# AirSystem8266PCB.net
KiCad netlist of a schematic drawn in Altium Designer
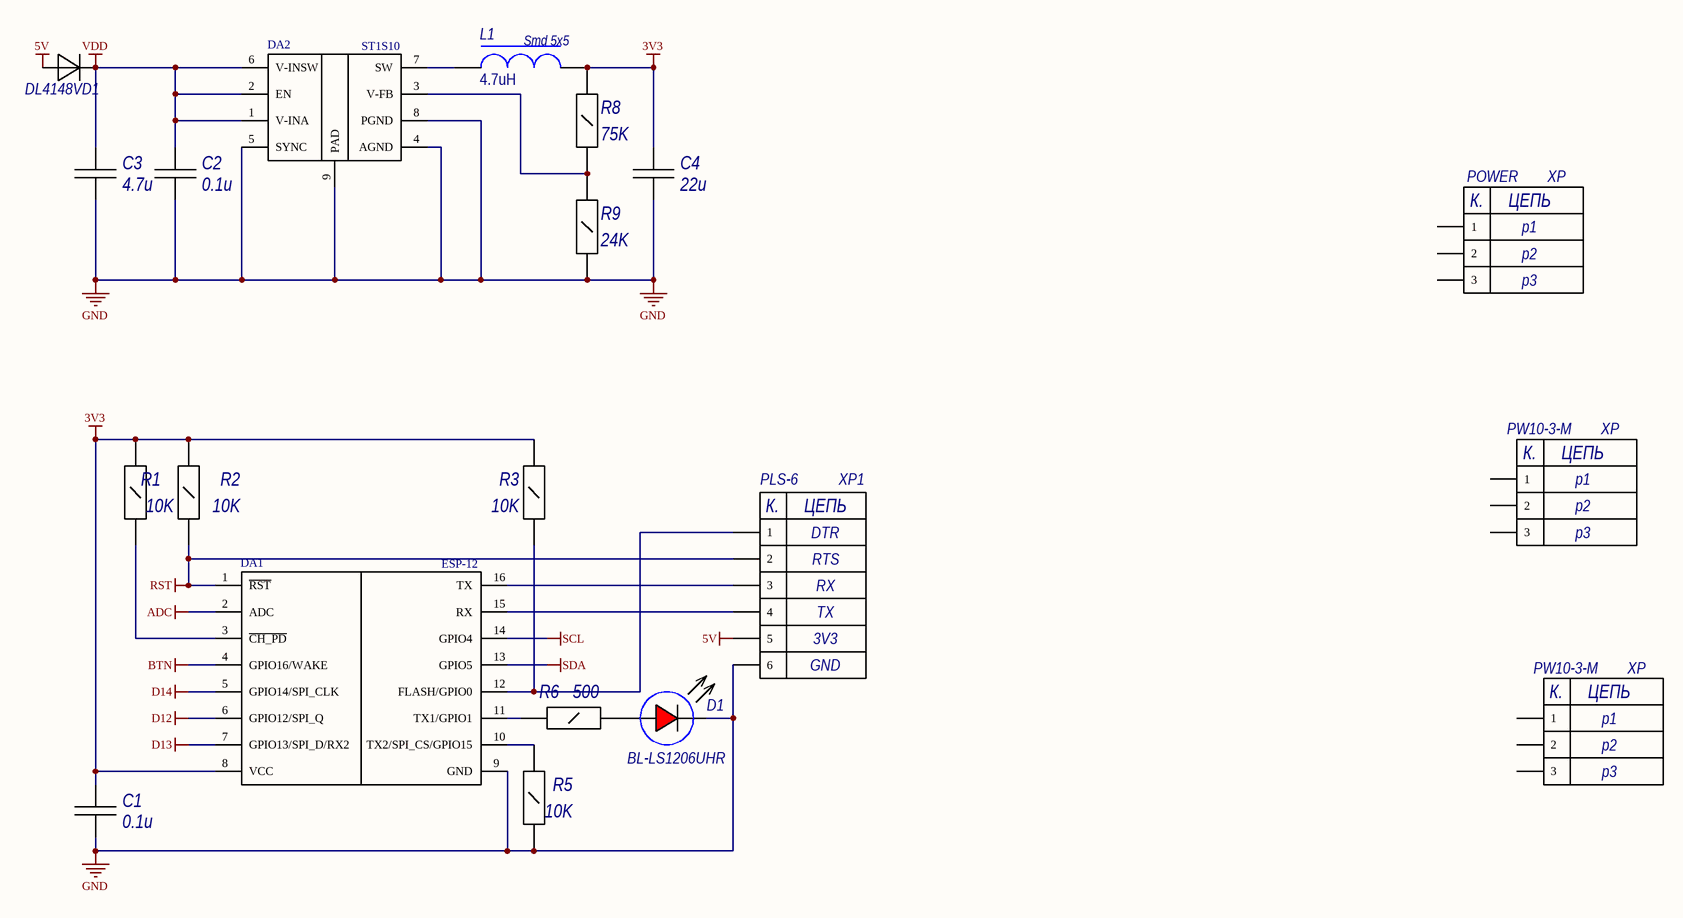
[diagram p0: AirSystem8266PCB.SchDoc]

(export (version "E")
  (design (tool "Eeschema 10.0.6"))
  (components
    (comp (ref "C1") (value "0.1u") (footprint "C1206") (libsource (lib "capacitors") (part "SMD_1206")))
    (comp (ref "C2") (value "0.1u") (footprint "C1206") (libsource (lib "capacitors") (part "SMD_1206")))
    (comp (ref "C3") (value "4.7u") (footprint "C1206") (libsource (lib "capacitors") (part "SMD_1206")))
    (comp (ref "C4") (value "22u") (footprint "C1206") (libsource (lib "capacitors") (part "SMD_1206")))
    (comp (ref "D1")
      (value "BL-LS1206UHR")
      (footprint "BL-LC1206")
      (libsource (lib "diodes") (part "KP-3216SURCK"))
    )
    (comp (ref "DA1") (value "ESP-12") (footprint "ESP-12") (libsource (lib "integral") (part "ESP-12")))
    (comp (ref "DA2")
      (value "ST1S10")
      (footprint "SO-8_Power")
      (libsource (lib "integral") (part "ST1S10 Step-down 3A"))
    )
    (comp (ref "L1") (value "4.7uH") (footprint "Smd 5x5") (libsource (lib "inductivity") (part "Smd 5x5")))
    (comp (ref "R1") (value "10K") (footprint "1206") (libsource (lib "rezistors") (part "1206")))
    (comp (ref "R2") (value "10K") (footprint "1206") (libsource (lib "rezistors") (part "1206")))
    (comp (ref "R3") (value "10K") (footprint "1206") (libsource (lib "rezistors") (part "1206")))
    (comp (ref "R5") (value "10K") (footprint "1206") (libsource (lib "rezistors") (part "1206")))
    (comp (ref "R6") (value "500") (footprint "1206") (libsource (lib "rezistors") (part "1206")))
    (comp (ref "R8") (value "75K") (footprint "1206") (libsource (lib "rezistors") (part "1206")))
    (comp (ref "R9") (value "24K") (footprint "1206") (libsource (lib "rezistors") (part "1206")))
    (comp (ref "VD1")
      (value "DL4148")
      (footprint "DO-213AA(SOD80)")
      (libsource (lib "diodes") (part "DL4148"))
    )
    (comp (ref "XP")
      (value "PW10-3-M")
      (footprint "PW10-3-M2")
      (fields (field (name "P1") "p1") (field (name "P2") "p2") (field (name "P3") "p3"))
      (libsource (lib "connectors") (part "PW10-3-M"))
    )
    (comp (ref "XP1")
      (value "PLS-6")
      (footprint "PLS-6_1")
      (fields
        (field (name "ALTIUM_UNNAMED_1") "DTR")
        (field (name "ALTIUM_UNNAMED_2") "RTS")
        (field (name "ALTIUM_UNNAMED_3") "RX")
        (field (name "ALTIUM_UNNAMED_4") "TX")
        (field (name "ALTIUM_UNNAMED_5") "3V3")
        (field (name "ALTIUM_UNNAMED_6") "GND")
      )
      (libsource (lib "connectors") (part "PLS-6"))
    )
  )
  (nets
    (net (code "1") (name "3V3") (class "Default")
      (node (ref "C1") (pin "1") (pinfunction "1_1") (pintype "passive"))
      (node (ref "C4") (pin "1") (pinfunction "1_1") (pintype "passive"))
      (node (ref "DA1") (pin "8") (pinfunction "VCC_8") (pintype "passive"))
      (node (ref "L1") (pin "2") (pinfunction "2_2") (pintype "passive"))
      (node (ref "R1") (pin "1") (pinfunction "1_1") (pintype "passive"))
      (node (ref "R2") (pin "1") (pinfunction "1_1") (pintype "passive"))
      (node (ref "R3") (pin "1") (pinfunction "1_1") (pintype "passive"))
      (node (ref "R8") (pin "2") (pinfunction "2_2") (pintype "passive"))
    )
    (net (code "2") (name "5V") (class "Default")
      (node (ref "VD1") (pin "2") (pinfunction "2_2") (pintype "passive"))
      (node (ref "XP1") (pin "5") (pinfunction "5_5") (pintype "passive"))
    )
    (net (code "3") (name "ADC") (class "Default")
      (node (ref "DA1") (pin "2") (pinfunction "ADC_2") (pintype "passive"))
    )
    (net (code "4") (name "BTN") (class "Default")
      (node (ref "DA1") (pin "4") (pinfunction "GPIO16/WAKE_4") (pintype "passive"))
    )
    (net (code "5") (name "D12") (class "Default")
      (node (ref "DA1") (pin "6") (pinfunction "GPIO12/SPI_Q_6") (pintype "passive"))
    )
    (net (code "6") (name "D13") (class "Default")
      (node (ref "DA1") (pin "7") (pinfunction "GPIO13/SPI_D/RX2_7") (pintype "passive"))
    )
    (net (code "7") (name "D14") (class "Default")
      (node (ref "DA1") (pin "5") (pinfunction "GPIO14/SPI_CLK_5") (pintype "passive"))
    )
    (net (code "8") (name "GND") (class "Default")
      (node (ref "C1") (pin "2") (pinfunction "2_2") (pintype "passive"))
      (node (ref "C2") (pin "2") (pinfunction "2_2") (pintype "passive"))
      (node (ref "C3") (pin "2") (pinfunction "2_2") (pintype "passive"))
      (node (ref "C4") (pin "2") (pinfunction "2_2") (pintype "passive"))
      (node (ref "D1") (pin "1") (pinfunction "1_1") (pintype "passive"))
      (node (ref "DA1") (pin "9") (pinfunction "GND_9") (pintype "passive"))
      (node (ref "DA2") (pin "4") (pinfunction "AGND_4") (pintype "passive"))
      (node (ref "DA2") (pin "5") (pinfunction "SYNC_5") (pintype "passive"))
      (node (ref "DA2") (pin "8") (pinfunction "PGND_8") (pintype "passive"))
      (node (ref "DA2") (pin "9") (pinfunction "PAD_9") (pintype "passive"))
      (node (ref "R5") (pin "2") (pinfunction "2_2") (pintype "passive"))
      (node (ref "R9") (pin "1") (pinfunction "1_1") (pintype "passive"))
      (node (ref "XP1") (pin "6") (pinfunction "6_6") (pintype "passive"))
    )
    (net (code "9") (name "Net-(D1-Pad2)") (class "Default")
      (node (ref "D1") (pin "2") (pinfunction "2_2") (pintype "passive"))
      (node (ref "R6") (pin "1") (pinfunction "1_1") (pintype "passive"))
    )
    (net (code "10") (name "Net-(DA1-FLASH{slash}GPIO0)") (class "Default")
      (node (ref "DA1") (pin "12") (pinfunction "FLASH/GPIO0_12") (pintype "passive"))
      (node (ref "R3") (pin "2") (pinfunction "2_2") (pintype "passive"))
      (node (ref "XP1") (pin "1") (pinfunction "1_1") (pintype "passive"))
    )
    (net (code "11") (name "Net-(DA1-RX)") (class "Default")
      (node (ref "DA1") (pin "15") (pinfunction "RX_15") (pintype "passive"))
      (node (ref "XP1") (pin "4") (pinfunction "4_4") (pintype "passive"))
    )
    (net (code "12") (name "Net-(DA1-TX)") (class "Default")
      (node (ref "DA1") (pin "16") (pinfunction "TX_16") (pintype "passive"))
      (node (ref "XP1") (pin "3") (pinfunction "3_3") (pintype "passive"))
    )
    (net (code "13") (name "Net-(DA1-TX1{slash}GPIO1)") (class "Default")
      (node (ref "DA1") (pin "11") (pinfunction "TX1/GPIO1_11") (pintype "passive"))
      (node (ref "R6") (pin "2") (pinfunction "2_2") (pintype "passive"))
    )
    (net (code "14") (name "Net-(DA1-TX2{slash}SPI_CS{slash}GPIO15)") (class "Default")
      (node (ref "DA1") (pin "10") (pinfunction "TX2/SPI_CS/GPIO15_10") (pintype "passive"))
      (node (ref "R5") (pin "1") (pinfunction "1_1") (pintype "passive"))
    )
    (net (code "15") (name "Net-(DA1-~{CH_PD})") (class "Default")
      (node (ref "DA1") (pin "3") (pinfunction "~{CH_PD}_3") (pintype "passive"))
      (node (ref "R1") (pin "2") (pinfunction "2_2") (pintype "passive"))
    )
    (net (code "16") (name "Net-(DA2-SW)") (class "Default")
      (node (ref "DA2") (pin "7") (pinfunction "SW_7") (pintype "passive"))
      (node (ref "L1") (pin "1") (pinfunction "1_1") (pintype "passive"))
    )
    (net (code "17") (name "Net-(DA2-V-FB)") (class "Default")
      (node (ref "DA2") (pin "3") (pinfunction "V-FB_3") (pintype "passive"))
      (node (ref "R8") (pin "1") (pinfunction "1_1") (pintype "passive"))
      (node (ref "R9") (pin "2") (pinfunction "2_2") (pintype "passive"))
    )
    (net (code "18") (name "RST") (class "Default")
      (node (ref "DA1") (pin "1") (pinfunction "~{RST}_1") (pintype "passive"))
      (node (ref "R2") (pin "2") (pinfunction "2_2") (pintype "passive"))
      (node (ref "XP1") (pin "2") (pinfunction "2_2") (pintype "passive"))
    )
    (net (code "19") (name "SCL") (class "Default")
      (node (ref "DA1") (pin "14") (pinfunction "GPIO4_14") (pintype "passive"))
    )
    (net (code "20") (name "SDA") (class "Default")
      (node (ref "DA1") (pin "13") (pinfunction "GPIO5_13") (pintype "passive"))
    )
    (net (code "21") (name "VDD") (class "Default")
      (node (ref "C2") (pin "1") (pinfunction "1_1") (pintype "passive"))
      (node (ref "C3") (pin "1") (pinfunction "1_1") (pintype "passive"))
      (node (ref "DA2") (pin "1") (pinfunction "V-INA_1") (pintype "passive"))
      (node (ref "DA2") (pin "2") (pinfunction "EN_2") (pintype "passive"))
      (node (ref "DA2") (pin "6") (pinfunction "V-INSW_6") (pintype "passive"))
      (node (ref "VD1") (pin "1") (pinfunction "1_1") (pintype "passive"))
    )
    (net (code "22") (name "unconnected-(XP-Pad1)") (class "Default")
      (node (ref "XP") (pin "1") (pinfunction "1_1") (pintype "passive"))
    )
    (net (code "23") (name "unconnected-(XP-Pad1)_1") (class "Default")
      (node (ref "XP") (pin "1") (pinfunction "1_1") (pintype "passive"))
    )
    (net (code "24") (name "unconnected-(XP-Pad1)_2") (class "Default")
      (node (ref "XP") (pin "1") (pinfunction "1_1") (pintype "passive"))
    )
    (net (code "25") (name "unconnected-(XP-Pad2)") (class "Default")
      (node (ref "XP") (pin "2") (pinfunction "2_2") (pintype "passive"))
    )
    (net (code "26") (name "unconnected-(XP-Pad2)_1") (class "Default")
      (node (ref "XP") (pin "2") (pinfunction "2_2") (pintype "passive"))
    )
    (net (code "27") (name "unconnected-(XP-Pad2)_2") (class "Default")
      (node (ref "XP") (pin "2") (pinfunction "2_2") (pintype "passive"))
    )
    (net (code "28") (name "unconnected-(XP-Pad3)") (class "Default")
      (node (ref "XP") (pin "3") (pinfunction "3_3") (pintype "passive"))
    )
    (net (code "29") (name "unconnected-(XP-Pad3)_1") (class "Default")
      (node (ref "XP") (pin "3") (pinfunction "3_3") (pintype "passive"))
    )
    (net (code "30") (name "unconnected-(XP-Pad3)_2") (class "Default")
      (node (ref "XP") (pin "3") (pinfunction "3_3") (pintype "passive"))
    )
  )
)
